# mega_pinout_4.net
KiCad netlist of a schematic drawn in EAGLE
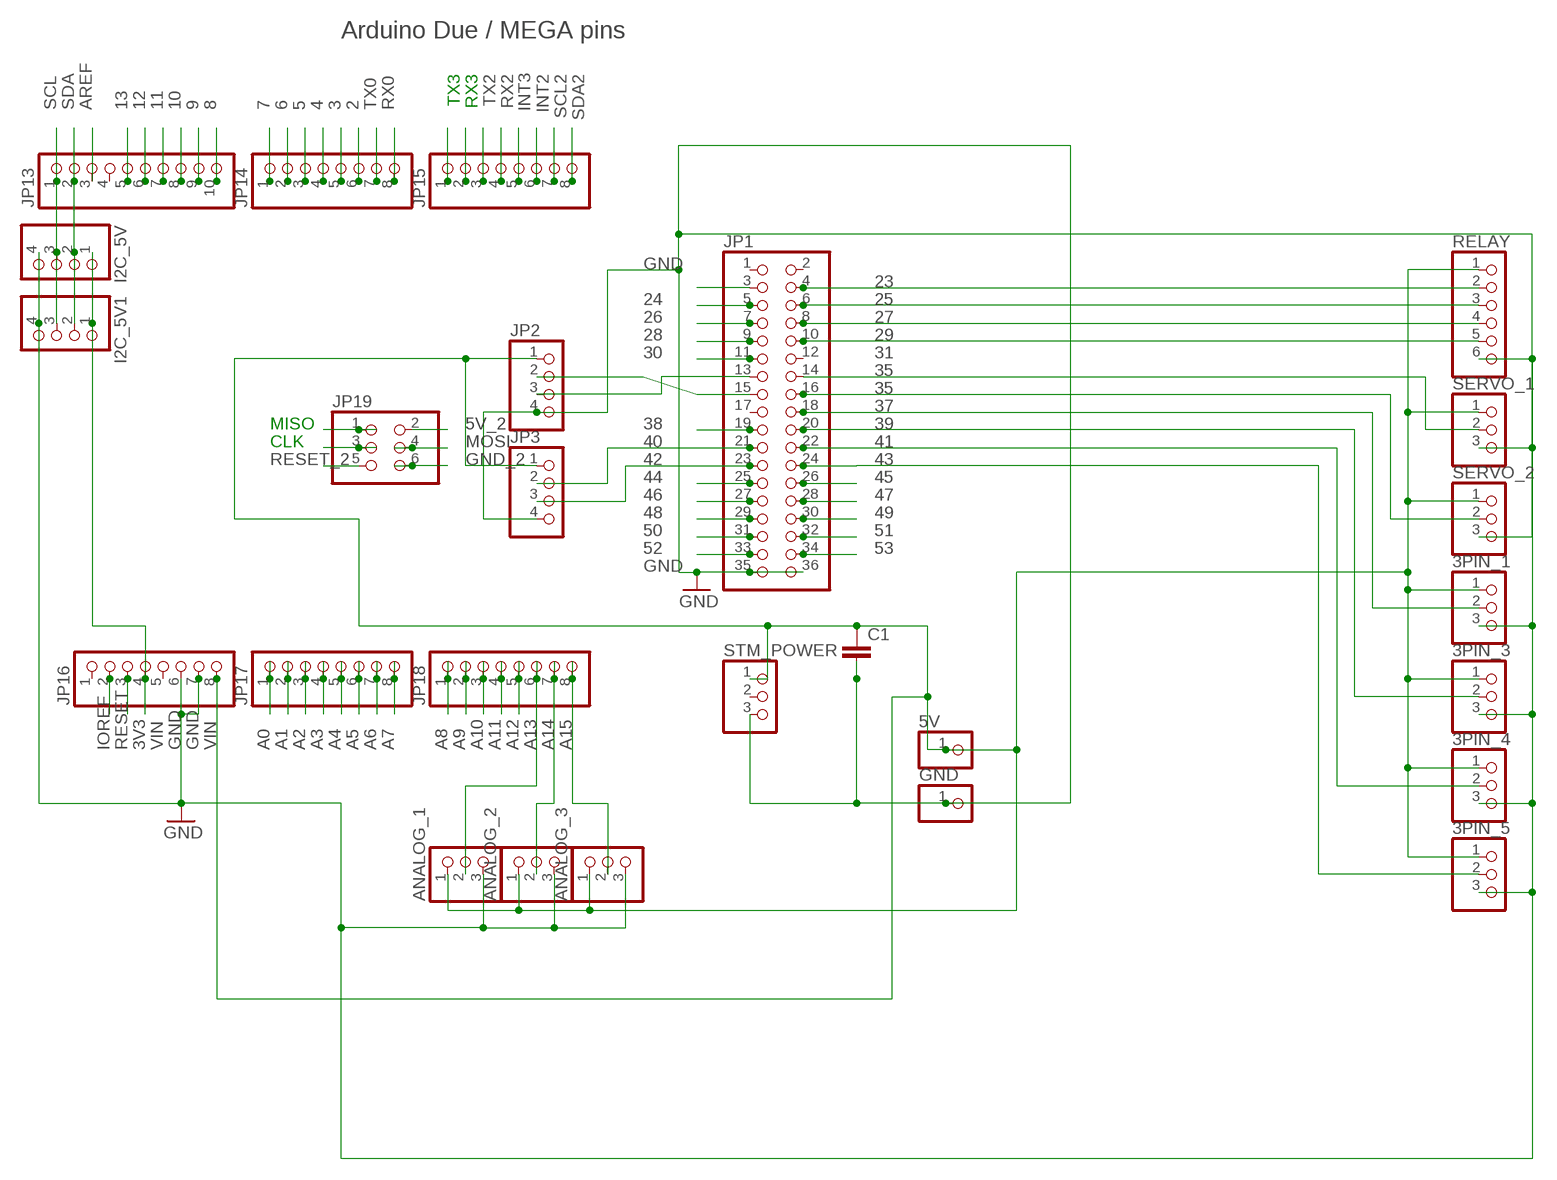
[diagram p0: schematic, sheet 1]

(export (version "E")
  (design (tool "Eeschema 10.0.6"))
  (components
    (comp (ref "3PIN_1")
      (value "PINHD-1X3")
      (footprint "eagle-import:1X03")
      (libsource (lib "eagle-import") (part "PINHD-1X3"))
    )
    (comp (ref "3PIN_3")
      (value "PINHD-1X3")
      (footprint "eagle-import:1X03")
      (libsource (lib "eagle-import") (part "PINHD-1X3"))
    )
    (comp (ref "3PIN_4")
      (value "PINHD-1X3")
      (footprint "eagle-import:1X03")
      (libsource (lib "eagle-import") (part "PINHD-1X3"))
    )
    (comp (ref "3PIN_5")
      (value "PINHD-1X3")
      (footprint "eagle-import:1X03")
      (libsource (lib "eagle-import") (part "PINHD-1X3"))
    )
    (comp (ref "5V")
      (value "PINHD-1X1")
      (footprint "eagle-import:1X01")
      (libsource (lib "eagle-import") (part "PINHD-1X1"))
    )
    (comp (ref "ANALOG_1")
      (value "PINHD-1X3")
      (footprint "eagle-import:1X03")
      (libsource (lib "eagle-import") (part "PINHD-1X3"))
    )
    (comp (ref "ANALOG_2")
      (value "PINHD-1X3")
      (footprint "eagle-import:1X03")
      (libsource (lib "eagle-import") (part "PINHD-1X3"))
    )
    (comp (ref "ANALOG_3")
      (value "PINHD-1X3")
      (footprint "eagle-import:1X03")
      (libsource (lib "eagle-import") (part "PINHD-1X3"))
    )
    (comp (ref "C1")
      (value "C-EU075-032X103")
      (footprint "eagle-import:C075-032X103")
      (libsource (lib "eagle-import") (part "C-EU075-032X103"))
    )
    (comp (ref "GND")
      (value "PINHD-1X1")
      (footprint "eagle-import:1X01")
      (libsource (lib "eagle-import") (part "PINHD-1X1"))
    )
    (comp (ref "I2C_5V")
      (value "PINHD-1X4")
      (footprint "eagle-import:1X04")
      (libsource (lib "eagle-import") (part "PINHD-1X4"))
    )
    (comp (ref "I2C_5V1")
      (value "PINHD-1X4")
      (footprint "eagle-import:1X04")
      (libsource (lib "eagle-import") (part "PINHD-1X4"))
    )
    (comp (ref "JP1")
      (value "PINHD-2X18")
      (footprint "eagle-import:2X18")
      (libsource (lib "eagle-import") (part "PINHD-2X18"))
    )
    (comp (ref "JP2")
      (value "PINHD-1X4")
      (footprint "eagle-import:1X04")
      (libsource (lib "eagle-import") (part "PINHD-1X4"))
    )
    (comp (ref "JP3")
      (value "PINHD-1X4")
      (footprint "eagle-import:1X04")
      (libsource (lib "eagle-import") (part "PINHD-1X4"))
    )
    (comp (ref "JP13")
      (value "PINHD-1X10")
      (footprint "eagle-import:1X10")
      (libsource (lib "eagle-import") (part "PINHD-1X10"))
    )
    (comp (ref "JP14")
      (value "PINHD-1X8")
      (footprint "eagle-import:1X08")
      (libsource (lib "eagle-import") (part "PINHD-1X8"))
    )
    (comp (ref "JP15")
      (value "PINHD-1X8")
      (footprint "eagle-import:1X08")
      (libsource (lib "eagle-import") (part "PINHD-1X8"))
    )
    (comp (ref "JP16")
      (value "PINHD-1X8")
      (footprint "eagle-import:1X08")
      (libsource (lib "eagle-import") (part "PINHD-1X8"))
    )
    (comp (ref "JP17")
      (value "PINHD-1X8")
      (footprint "eagle-import:1X08")
      (libsource (lib "eagle-import") (part "PINHD-1X8"))
    )
    (comp (ref "JP18")
      (value "PINHD-1X8")
      (footprint "eagle-import:1X08")
      (libsource (lib "eagle-import") (part "PINHD-1X8"))
    )
    (comp (ref "JP19")
      (value "PINHD-2X3")
      (footprint "eagle-import:2X03")
      (libsource (lib "eagle-import") (part "PINHD-2X3"))
    )
    (comp (ref "RELAY")
      (value "PINHD-1X6")
      (footprint "eagle-import:1X06")
      (libsource (lib "eagle-import") (part "PINHD-1X6"))
    )
    (comp (ref "SERVO_1")
      (value "PINHD-1X3")
      (footprint "eagle-import:1X03")
      (libsource (lib "eagle-import") (part "PINHD-1X3"))
    )
    (comp (ref "SERVO_2")
      (value "PINHD-1X3")
      (footprint "eagle-import:1X03")
      (libsource (lib "eagle-import") (part "PINHD-1X3"))
    )
    (comp (ref "STM_POWER")
      (value "PINHD-1X3")
      (footprint "eagle-import:1X03")
      (libsource (lib "eagle-import") (part "PINHD-1X3"))
    )
  )
  (nets
    (net (code "1") (name "/2") (class "Default")
      (node (ref "JP14") (pin "6") (pinfunction "6_6") (pintype "passive"))
    )
    (net (code "2") (name "/3") (class "Default")
      (node (ref "JP14") (pin "5") (pinfunction "5_5") (pintype "passive"))
    )
    (net (code "3") (name "/3V3") (class "Default")
      (node (ref "I2C_5V") (pin "1") (pinfunction "1_1") (pintype "passive"))
      (node (ref "I2C_5V1") (pin "1") (pinfunction "1_1") (pintype "passive"))
      (node (ref "JP16") (pin "4") (pinfunction "4_4") (pintype "passive"))
    )
    (net (code "4") (name "/4") (class "Default")
      (node (ref "JP14") (pin "4") (pinfunction "4_4") (pintype "passive"))
    )
    (net (code "5") (name "/5") (class "Default")
      (node (ref "JP14") (pin "3") (pinfunction "3_3") (pintype "passive"))
    )
    (net (code "6") (name "/5V_2") (class "Default")
      (node (ref "JP19") (pin "2") (pinfunction "2_2") (pintype "passive"))
    )
    (net (code "7") (name "/6") (class "Default")
      (node (ref "JP14") (pin "2") (pinfunction "2_2") (pintype "passive"))
    )
    (net (code "8") (name "/7") (class "Default")
      (node (ref "JP14") (pin "1") (pinfunction "1_1") (pintype "passive"))
    )
    (net (code "9") (name "/8") (class "Default")
      (node (ref "JP13") (pin "10") (pinfunction "10_10") (pintype "passive"))
    )
    (net (code "10") (name "/9") (class "Default")
      (node (ref "JP13") (pin "9") (pinfunction "9_9") (pintype "passive"))
    )
    (net (code "11") (name "/10") (class "Default")
      (node (ref "JP13") (pin "8") (pinfunction "8_8") (pintype "passive"))
    )
    (net (code "12") (name "/11") (class "Default")
      (node (ref "JP13") (pin "7") (pinfunction "7_7") (pintype "passive"))
    )
    (net (code "13") (name "/12") (class "Default")
      (node (ref "JP13") (pin "6") (pinfunction "6_6") (pintype "passive"))
    )
    (net (code "14") (name "/13") (class "Default")
      (node (ref "JP13") (pin "5") (pinfunction "5_5") (pintype "passive"))
    )
    (net (code "15") (name "/23") (class "Default")
      (node (ref "JP1") (pin "4") (pinfunction "4_4") (pintype "passive"))
      (node (ref "RELAY") (pin "2") (pinfunction "2_2") (pintype "passive"))
    )
    (net (code "16") (name "/24") (class "Default")
      (node (ref "JP1") (pin "5") (pinfunction "5_5") (pintype "passive"))
    )
    (net (code "17") (name "/25") (class "Default")
      (node (ref "JP1") (pin "6") (pinfunction "6_6") (pintype "passive"))
      (node (ref "RELAY") (pin "3") (pinfunction "3_3") (pintype "passive"))
    )
    (net (code "18") (name "/26") (class "Default")
      (node (ref "JP1") (pin "7") (pinfunction "7_7") (pintype "passive"))
    )
    (net (code "19") (name "/27") (class "Default")
      (node (ref "JP1") (pin "8") (pinfunction "8_8") (pintype "passive"))
      (node (ref "RELAY") (pin "4") (pinfunction "4_4") (pintype "passive"))
    )
    (net (code "20") (name "/28") (class "Default")
      (node (ref "JP1") (pin "9") (pinfunction "9_9") (pintype "passive"))
    )
    (net (code "21") (name "/29") (class "Default")
      (node (ref "JP1") (pin "10") (pinfunction "10_10") (pintype "passive"))
      (node (ref "RELAY") (pin "5") (pinfunction "5_5") (pintype "passive"))
    )
    (net (code "22") (name "/30") (class "Default")
      (node (ref "JP1") (pin "11") (pinfunction "11_11") (pintype "passive"))
    )
    (net (code "23") (name "/31") (class "Default")
      (node (ref "JP1") (pin "14") (pinfunction "14_14") (pintype "passive"))
      (node (ref "SERVO_1") (pin "2") (pinfunction "2_2") (pintype "passive"))
    )
    (net (code "24") (name "/35") (class "Default")
      (node (ref "JP1") (pin "16") (pinfunction "16_16") (pintype "passive"))
      (node (ref "SERVO_2") (pin "2") (pinfunction "2_2") (pintype "passive"))
    )
    (net (code "25") (name "/37") (class "Default")
      (node (ref "3PIN_1") (pin "2") (pinfunction "2_2") (pintype "passive"))
      (node (ref "JP1") (pin "18") (pinfunction "18_18") (pintype "passive"))
    )
    (net (code "26") (name "/38") (class "Default")
      (node (ref "JP1") (pin "19") (pinfunction "19_19") (pintype "passive"))
    )
    (net (code "27") (name "/39") (class "Default")
      (node (ref "3PIN_3") (pin "2") (pinfunction "2_2") (pintype "passive"))
      (node (ref "JP1") (pin "20") (pinfunction "20_20") (pintype "passive"))
    )
    (net (code "28") (name "/40") (class "Default")
      (node (ref "JP1") (pin "21") (pinfunction "21_21") (pintype "passive"))
      (node (ref "JP3") (pin "2") (pinfunction "2_2") (pintype "passive"))
    )
    (net (code "29") (name "/41") (class "Default")
      (node (ref "3PIN_4") (pin "2") (pinfunction "2_2") (pintype "passive"))
      (node (ref "JP1") (pin "22") (pinfunction "22_22") (pintype "passive"))
    )
    (net (code "30") (name "/42") (class "Default")
      (node (ref "JP1") (pin "23") (pinfunction "23_23") (pintype "passive"))
      (node (ref "JP3") (pin "3") (pinfunction "3_3") (pintype "passive"))
    )
    (net (code "31") (name "/43") (class "Default")
      (node (ref "3PIN_5") (pin "2") (pinfunction "2_2") (pintype "passive"))
      (node (ref "JP1") (pin "24") (pinfunction "24_24") (pintype "passive"))
    )
    (net (code "32") (name "/44") (class "Default")
      (node (ref "JP1") (pin "25") (pinfunction "25_25") (pintype "passive"))
    )
    (net (code "33") (name "/45") (class "Default")
      (node (ref "JP1") (pin "26") (pinfunction "26_26") (pintype "passive"))
    )
    (net (code "34") (name "/46") (class "Default")
      (node (ref "JP1") (pin "27") (pinfunction "27_27") (pintype "passive"))
    )
    (net (code "35") (name "/47") (class "Default")
      (node (ref "JP1") (pin "28") (pinfunction "28_28") (pintype "passive"))
    )
    (net (code "36") (name "/48") (class "Default")
      (node (ref "JP1") (pin "29") (pinfunction "29_29") (pintype "passive"))
    )
    (net (code "37") (name "/49") (class "Default")
      (node (ref "JP1") (pin "30") (pinfunction "30_30") (pintype "passive"))
    )
    (net (code "38") (name "/50") (class "Default")
      (node (ref "JP1") (pin "31") (pinfunction "31_31") (pintype "passive"))
    )
    (net (code "39") (name "/51") (class "Default")
      (node (ref "JP1") (pin "32") (pinfunction "32_32") (pintype "passive"))
    )
    (net (code "40") (name "/52") (class "Default")
      (node (ref "JP1") (pin "33") (pinfunction "33_33") (pintype "passive"))
    )
    (net (code "41") (name "/53") (class "Default")
      (node (ref "JP1") (pin "34") (pinfunction "34_34") (pintype "passive"))
    )
    (net (code "42") (name "/A0") (class "Default")
      (node (ref "JP17") (pin "1") (pinfunction "1_1") (pintype "passive"))
    )
    (net (code "43") (name "/A1") (class "Default")
      (node (ref "JP17") (pin "2") (pinfunction "2_2") (pintype "passive"))
    )
    (net (code "44") (name "/A2") (class "Default")
      (node (ref "JP17") (pin "3") (pinfunction "3_3") (pintype "passive"))
    )
    (net (code "45") (name "/A3") (class "Default")
      (node (ref "JP17") (pin "4") (pinfunction "4_4") (pintype "passive"))
    )
    (net (code "46") (name "/A4") (class "Default")
      (node (ref "JP17") (pin "5") (pinfunction "5_5") (pintype "passive"))
    )
    (net (code "47") (name "/A5") (class "Default")
      (node (ref "JP17") (pin "6") (pinfunction "6_6") (pintype "passive"))
    )
    (net (code "48") (name "/A6") (class "Default")
      (node (ref "JP17") (pin "7") (pinfunction "7_7") (pintype "passive"))
    )
    (net (code "49") (name "/A7") (class "Default")
      (node (ref "JP17") (pin "8") (pinfunction "8_8") (pintype "passive"))
    )
    (net (code "50") (name "/A8") (class "Default")
      (node (ref "JP18") (pin "1") (pinfunction "1_1") (pintype "passive"))
    )
    (net (code "51") (name "/A9") (class "Default")
      (node (ref "JP18") (pin "2") (pinfunction "2_2") (pintype "passive"))
    )
    (net (code "52") (name "/A10") (class "Default")
      (node (ref "JP18") (pin "3") (pinfunction "3_3") (pintype "passive"))
    )
    (net (code "53") (name "/A11") (class "Default")
      (node (ref "JP18") (pin "4") (pinfunction "4_4") (pintype "passive"))
    )
    (net (code "54") (name "/A12") (class "Default")
      (node (ref "JP18") (pin "5") (pinfunction "5_5") (pintype "passive"))
    )
    (net (code "55") (name "/A13") (class "Default")
      (node (ref "ANALOG_1") (pin "2") (pinfunction "2_2") (pintype "passive"))
      (node (ref "JP18") (pin "6") (pinfunction "6_6") (pintype "passive"))
    )
    (net (code "56") (name "/A14") (class "Default")
      (node (ref "ANALOG_2") (pin "2") (pinfunction "2_2") (pintype "passive"))
      (node (ref "JP18") (pin "7") (pinfunction "7_7") (pintype "passive"))
    )
    (net (code "57") (name "/A15") (class "Default")
      (node (ref "ANALOG_3") (pin "2") (pinfunction "2_2") (pintype "passive"))
      (node (ref "JP18") (pin "8") (pinfunction "8_8") (pintype "passive"))
    )
    (net (code "58") (name "/AREF") (class "Default")
      (node (ref "JP13") (pin "3") (pinfunction "3_3") (pintype "passive"))
    )
    (net (code "59") (name "/CLK") (class "Default")
      (node (ref "JP19") (pin "3") (pinfunction "3_3") (pintype "passive"))
    )
    (net (code "60") (name "/GND_2") (class "Default")
      (node (ref "JP19") (pin "6") (pinfunction "6_6") (pintype "passive"))
    )
    (net (code "61") (name "/INT2") (class "Default")
      (node (ref "JP15") (pin "6") (pinfunction "6_6") (pintype "passive"))
    )
    (net (code "62") (name "/INT3") (class "Default")
      (node (ref "JP15") (pin "5") (pinfunction "5_5") (pintype "passive"))
    )
    (net (code "63") (name "/IOREF") (class "Default")
      (node (ref "JP16") (pin "2") (pinfunction "2_2") (pintype "passive"))
    )
    (net (code "64") (name "/MISO") (class "Default")
      (node (ref "JP19") (pin "1") (pinfunction "1_1") (pintype "passive"))
    )
    (net (code "65") (name "/MOSI") (class "Default")
      (node (ref "JP19") (pin "4") (pinfunction "4_4") (pintype "passive"))
    )
    (net (code "66") (name "/RESET") (class "Default")
      (node (ref "JP16") (pin "3") (pinfunction "3_3") (pintype "passive"))
    )
    (net (code "67") (name "/RESET_2") (class "Default")
      (node (ref "JP19") (pin "5") (pinfunction "5_5") (pintype "passive"))
    )
    (net (code "68") (name "/RX0") (class "Default")
      (node (ref "JP14") (pin "8") (pinfunction "8_8") (pintype "passive"))
    )
    (net (code "69") (name "/RX2") (class "Default")
      (node (ref "JP15") (pin "4") (pinfunction "4_4") (pintype "passive"))
    )
    (net (code "70") (name "/RX3") (class "Default")
      (node (ref "JP15") (pin "2") (pinfunction "2_2") (pintype "passive"))
    )
    (net (code "71") (name "/SCL") (class "Default")
      (node (ref "I2C_5V") (pin "3") (pinfunction "3_3") (pintype "passive"))
      (node (ref "I2C_5V1") (pin "3") (pinfunction "3_3") (pintype "passive"))
      (node (ref "JP13") (pin "1") (pinfunction "1_1") (pintype "passive"))
    )
    (net (code "72") (name "/SCL2") (class "Default")
      (node (ref "JP15") (pin "7") (pinfunction "7_7") (pintype "passive"))
    )
    (net (code "73") (name "/SDA") (class "Default")
      (node (ref "I2C_5V") (pin "2") (pinfunction "2_2") (pintype "passive"))
      (node (ref "I2C_5V1") (pin "2") (pinfunction "2_2") (pintype "passive"))
      (node (ref "JP13") (pin "2") (pinfunction "2_2") (pintype "passive"))
    )
    (net (code "74") (name "/SDA2") (class "Default")
      (node (ref "JP15") (pin "8") (pinfunction "8_8") (pintype "passive"))
    )
    (net (code "75") (name "/TX0") (class "Default")
      (node (ref "JP14") (pin "7") (pinfunction "7_7") (pintype "passive"))
    )
    (net (code "76") (name "/TX2") (class "Default")
      (node (ref "JP15") (pin "3") (pinfunction "3_3") (pintype "passive"))
    )
    (net (code "77") (name "/TX3") (class "Default")
      (node (ref "JP15") (pin "1") (pinfunction "1_1") (pintype "passive"))
    )
    (net (code "78") (name "/VIN") (class "Default")
      (node (ref "3PIN_1") (pin "1") (pinfunction "1_1") (pintype "passive"))
      (node (ref "3PIN_3") (pin "1") (pinfunction "1_1") (pintype "passive"))
      (node (ref "3PIN_4") (pin "1") (pinfunction "1_1") (pintype "passive"))
      (node (ref "3PIN_5") (pin "1") (pinfunction "1_1") (pintype "passive"))
      (node (ref "5V") (pin "1") (pinfunction "1_1") (pintype "passive"))
      (node (ref "ANALOG_1") (pin "1") (pinfunction "1_1") (pintype "passive"))
      (node (ref "ANALOG_2") (pin "1") (pinfunction "1_1") (pintype "passive"))
      (node (ref "ANALOG_3") (pin "1") (pinfunction "1_1") (pintype "passive"))
      (node (ref "C1") (pin "1") (pinfunction "1_1") (pintype "passive"))
      (node (ref "JP16") (pin "8") (pinfunction "8_8") (pintype "passive"))
      (node (ref "JP2") (pin "1") (pinfunction "1_1") (pintype "passive"))
      (node (ref "JP3") (pin "1") (pinfunction "1_1") (pintype "passive"))
      (node (ref "RELAY") (pin "1") (pinfunction "1_1") (pintype "passive"))
      (node (ref "SERVO_1") (pin "1") (pinfunction "1_1") (pintype "passive"))
      (node (ref "SERVO_2") (pin "1") (pinfunction "1_1") (pintype "passive"))
      (node (ref "STM_POWER") (pin "1") (pinfunction "1_1") (pintype "passive"))
    )
    (net (code "79") (name "GND") (class "Default")
      (node (ref "3PIN_1") (pin "3") (pinfunction "3_3") (pintype "passive"))
      (node (ref "3PIN_3") (pin "3") (pinfunction "3_3") (pintype "passive"))
      (node (ref "3PIN_4") (pin "3") (pinfunction "3_3") (pintype "passive"))
      (node (ref "3PIN_5") (pin "3") (pinfunction "3_3") (pintype "passive"))
      (node (ref "ANALOG_1") (pin "3") (pinfunction "3_3") (pintype "passive"))
      (node (ref "ANALOG_2") (pin "3") (pinfunction "3_3") (pintype "passive"))
      (node (ref "ANALOG_3") (pin "3") (pinfunction "3_3") (pintype "passive"))
      (node (ref "C1") (pin "2") (pinfunction "2_2") (pintype "passive"))
      (node (ref "GND") (pin "1") (pinfunction "1_1") (pintype "passive"))
      (node (ref "I2C_5V") (pin "4") (pinfunction "4_4") (pintype "passive"))
      (node (ref "I2C_5V1") (pin "4") (pinfunction "4_4") (pintype "passive"))
      (node (ref "JP1") (pin "35") (pinfunction "35_35") (pintype "passive"))
      (node (ref "JP1") (pin "36") (pinfunction "36_36") (pintype "passive"))
      (node (ref "JP16") (pin "6") (pinfunction "6_6") (pintype "passive"))
      (node (ref "JP16") (pin "7") (pinfunction "7_7") (pintype "passive"))
      (node (ref "JP2") (pin "4") (pinfunction "4_4") (pintype "passive"))
      (node (ref "JP3") (pin "4") (pinfunction "4_4") (pintype "passive"))
      (node (ref "RELAY") (pin "6") (pinfunction "6_6") (pintype "passive"))
      (node (ref "SERVO_1") (pin "3") (pinfunction "3_3") (pintype "passive"))
      (node (ref "SERVO_2") (pin "3") (pinfunction "3_3") (pintype "passive"))
      (node (ref "STM_POWER") (pin "3") (pinfunction "3_3") (pintype "passive"))
    )
    (net (code "80") (name "Net-(JP1-Pad13)") (class "Default")
      (node (ref "JP1") (pin "13") (pinfunction "13_13") (pintype "passive"))
      (node (ref "JP2") (pin "3") (pinfunction "3_3") (pintype "passive"))
    )
    (net (code "81") (name "Net-(JP1-Pad15)") (class "Default")
      (node (ref "JP1") (pin "15") (pinfunction "15_15") (pintype "passive"))
      (node (ref "JP2") (pin "2") (pinfunction "2_2") (pintype "passive"))
    )
    (net (code "82") (name "unconnected-(JP1-Pad1)") (class "Default")
      (node (ref "JP1") (pin "1") (pinfunction "1_1") (pintype "passive"))
    )
    (net (code "83") (name "unconnected-(JP1-Pad2)") (class "Default")
      (node (ref "JP1") (pin "2") (pinfunction "2_2") (pintype "passive"))
    )
    (net (code "84") (name "unconnected-(JP1-Pad3)") (class "Default")
      (node (ref "JP1") (pin "3") (pinfunction "3_3") (pintype "passive"))
    )
    (net (code "85") (name "unconnected-(JP1-Pad12)") (class "Default")
      (node (ref "JP1") (pin "12") (pinfunction "12_12") (pintype "passive"))
    )
    (net (code "86") (name "unconnected-(JP1-Pad17)") (class "Default")
      (node (ref "JP1") (pin "17") (pinfunction "17_17") (pintype "passive"))
    )
    (net (code "87") (name "unconnected-(JP13-Pad4)") (class "Default")
      (node (ref "JP13") (pin "4") (pinfunction "4_4") (pintype "passive"))
    )
    (net (code "88") (name "unconnected-(JP16-Pad1)") (class "Default")
      (node (ref "JP16") (pin "1") (pinfunction "1_1") (pintype "passive"))
    )
    (net (code "89") (name "unconnected-(JP16-Pad5)") (class "Default")
      (node (ref "JP16") (pin "5") (pinfunction "5_5") (pintype "passive"))
    )
    (net (code "90") (name "unconnected-(STM_POWER-Pad2)") (class "Default")
      (node (ref "STM_POWER") (pin "2") (pinfunction "2_2") (pintype "passive"))
    )
  )
)
